# atmegaArduino.net
KiCad netlist of a schematic drawn in EAGLE
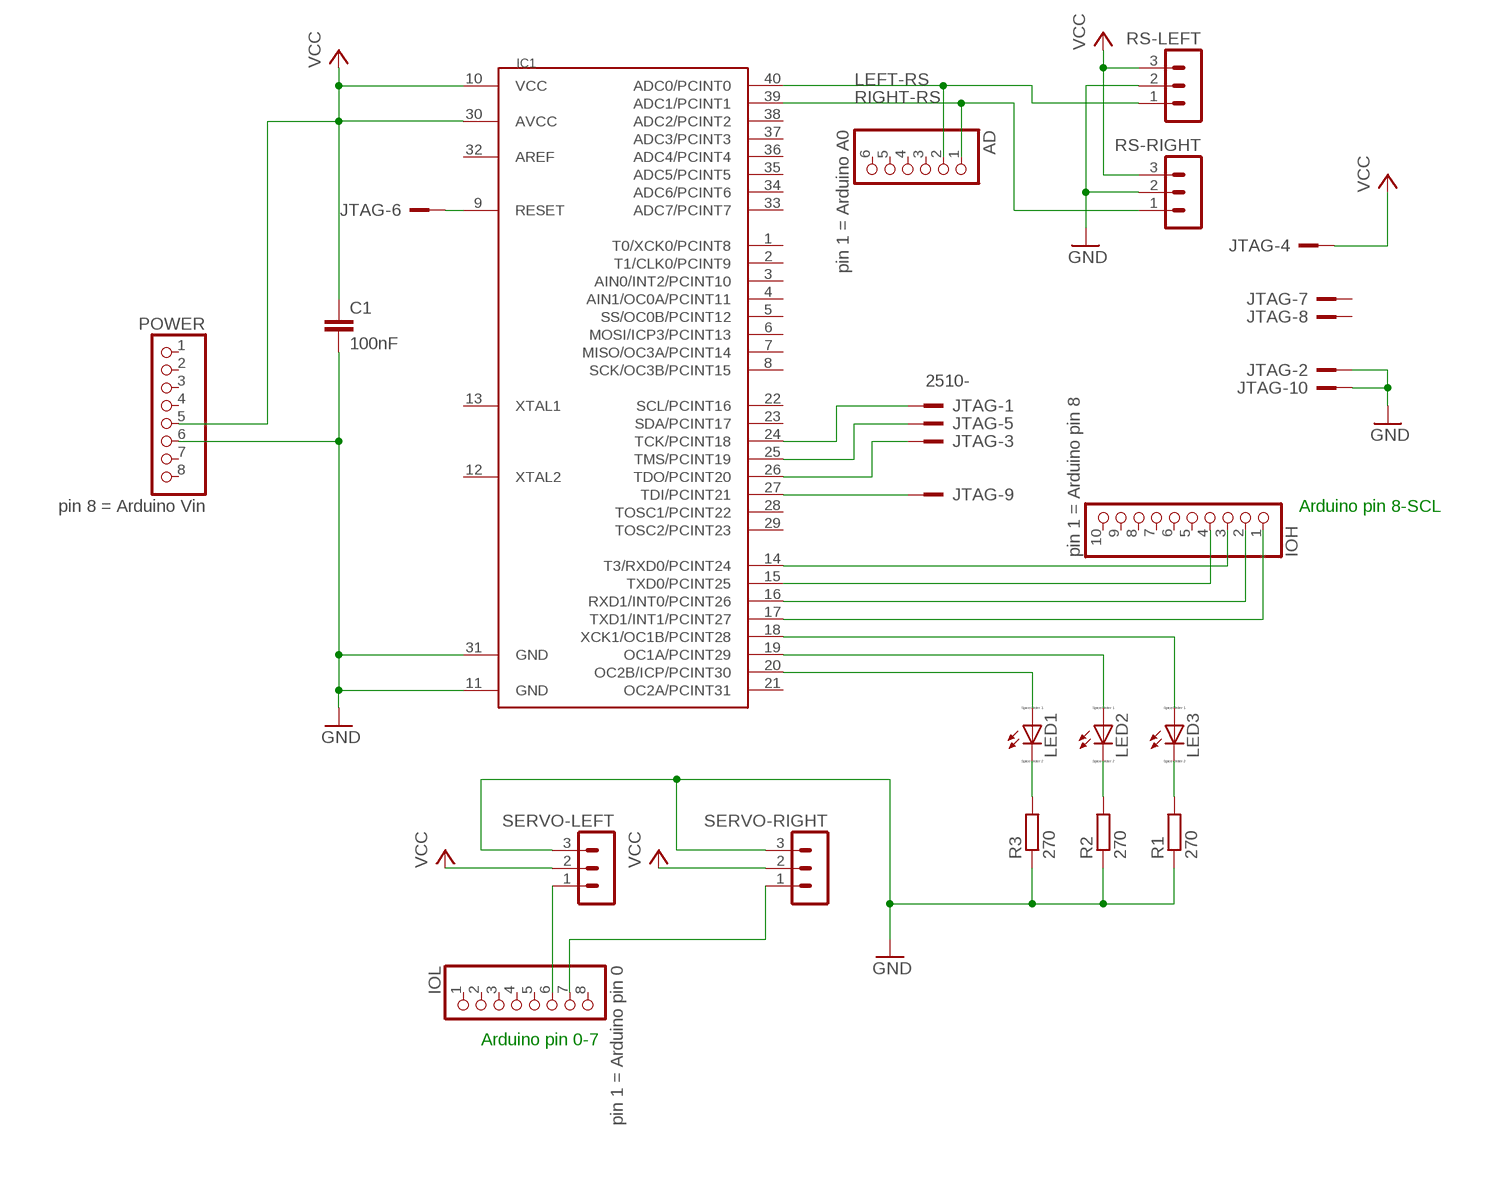
[diagram p0: schematic, sheet 1]

(export (version "E")
  (design (tool "Eeschema 10.0.6"))
  (components
    (comp (ref "AD")
      (value "pin 1 = Arduino A0")
      (footprint "eagle-import:1X06_90")
      (libsource (lib "eagle-import") (part "PINHD-1X6/90"))
    )
    (comp (ref "C1")
      (value "100nF")
      (footprint "eagle-import:C050-025X075")
      (libsource (lib "eagle-import") (part "C-EU050-025X075"))
    )
    (comp (ref "IC1")
      (value "MEGA1284P")
      (footprint "eagle-import:DIL40")
      (libsource (lib "eagle-import") (part "MEGA1284P"))
    )
    (comp (ref "IOH")
      (value "pin 1 = Arduino pin 8")
      (footprint "eagle-import:1X10_90")
      (libsource (lib "eagle-import") (part "PINHD-1X10/90"))
    )
    (comp (ref "IOL")
      (value "pin 1 = Arduino pin 0")
      (footprint "eagle-import:1X08_90")
      (libsource (lib "eagle-import") (part "PINHD-1X8/90"))
    )
    (comp (ref "JTAG")
      (value "2510-")
      (footprint "eagle-import:PAK100_2500-10")
      (fields (field (name "MF") "3M") (field (name "MPN") "2510-6002UB"))
      (libsource (lib "eagle-import") (part "2510-"))
    )
    (comp (ref "LED1")
      (value "LED_ELD260")
      (footprint "eagle-import:LED_LD260")
      (libsource (lib "eagle-import") (part "LED_ELD260"))
    )
    (comp (ref "LED2")
      (value "LED_ELD260")
      (footprint "eagle-import:LED_LD260")
      (libsource (lib "eagle-import") (part "LED_ELD260"))
    )
    (comp (ref "LED3")
      (value "LED_ELD260")
      (footprint "eagle-import:LED_LD260")
      (libsource (lib "eagle-import") (part "LED_ELD260"))
    )
    (comp (ref "POWER")
      (value "pin 8 = Arduino Vin")
      (footprint "eagle-import:1X08_90")
      (libsource (lib "eagle-import") (part "PINHD-1X8/90"))
    )
    (comp (ref "R1")
      (value "270")
      (footprint "eagle-import:0204_5")
      (libsource (lib "eagle-import") (part "R-EU_0204/5"))
    )
    (comp (ref "R2")
      (value "270")
      (footprint "eagle-import:0204_5")
      (libsource (lib "eagle-import") (part "R-EU_0204/5"))
    )
    (comp (ref "R3")
      (value "270")
      (footprint "eagle-import:0204_5")
      (libsource (lib "eagle-import") (part "R-EU_0204/5"))
    )
    (comp (ref "RS-LEFT")
      (value "MA03-1")
      (footprint "eagle-import:MA03-1")
      (libsource (lib "eagle-import") (part "MA03-1"))
    )
    (comp (ref "RS-RIGHT")
      (value "MA03-1")
      (footprint "eagle-import:MA03-1")
      (libsource (lib "eagle-import") (part "MA03-1"))
    )
    (comp (ref "SERVO-LEFT")
      (value "MA03-1")
      (footprint "eagle-import:MA03-1")
      (libsource (lib "eagle-import") (part "MA03-1"))
    )
    (comp (ref "SERVO-RIGHT")
      (value "MA03-1")
      (footprint "eagle-import:MA03-1")
      (libsource (lib "eagle-import") (part "MA03-1"))
    )
  )
  (nets
    (net (code "1") (name "/LEFT-RS") (class "Default")
      (node (ref "AD") (pin "2") (pinfunction "2_2") (pintype "passive"))
      (node (ref "IC1") (pin "40") (pinfunction "ADC0/PCINT0_40") (pintype "bidirectional"))
      (node (ref "RS-LEFT") (pin "1") (pinfunction "1_1") (pintype "passive"))
    )
    (net (code "2") (name "/RIGHT-RS") (class "Default")
      (node (ref "AD") (pin "1") (pinfunction "1_1") (pintype "passive"))
      (node (ref "IC1") (pin "39") (pinfunction "ADC1/PCINT1_39") (pintype "bidirectional"))
      (node (ref "RS-RIGHT") (pin "1") (pinfunction "1_1") (pintype "passive"))
    )
    (net (code "3") (name "GND") (class "Default")
      (node (ref "C1") (pin "2") (pinfunction "2_2") (pintype "passive"))
      (node (ref "IC1") (pin "11") (pinfunction "GND_11") (pintype "bidirectional"))
      (node (ref "IC1") (pin "31") (pinfunction "GND_31") (pintype "bidirectional"))
      (node (ref "JTAG") (pin "10") (pinfunction "KL_10") (pintype "passive"))
      (node (ref "JTAG") (pin "2") (pinfunction "KL_2") (pintype "passive"))
      (node (ref "POWER") (pin "6") (pinfunction "6_6") (pintype "passive"))
      (node (ref "R1") (pin "1") (pinfunction "1_1") (pintype "passive"))
      (node (ref "R2") (pin "1") (pinfunction "1_1") (pintype "passive"))
      (node (ref "R3") (pin "1") (pinfunction "1_1") (pintype "passive"))
      (node (ref "RS-LEFT") (pin "2") (pinfunction "2_2") (pintype "passive"))
      (node (ref "RS-RIGHT") (pin "2") (pinfunction "2_2") (pintype "passive"))
      (node (ref "SERVO-LEFT") (pin "3") (pinfunction "3_3") (pintype "passive"))
      (node (ref "SERVO-RIGHT") (pin "3") (pinfunction "3_3") (pintype "passive"))
    )
    (net (code "4") (name "Net-(IC1-OC1A{slash}PCINT29)") (class "Default")
      (node (ref "IC1") (pin "19") (pinfunction "OC1A/PCINT29_19") (pintype "bidirectional"))
      (node (ref "LED2") (pin "A") (pinfunction "A_A") (pintype "passive"))
    )
    (net (code "5") (name "Net-(IC1-OC2B{slash}ICP{slash}PCINT30)") (class "Default")
      (node (ref "IC1") (pin "20") (pinfunction "OC2B/ICP/PCINT30_20") (pintype "bidirectional"))
      (node (ref "LED1") (pin "A") (pinfunction "A_A") (pintype "passive"))
    )
    (net (code "6") (name "Net-(IC1-RESET)") (class "Default")
      (node (ref "IC1") (pin "9") (pinfunction "RESET_9") (pintype "bidirectional"))
      (node (ref "JTAG") (pin "6") (pinfunction "KL_6") (pintype "passive"))
    )
    (net (code "7") (name "Net-(IC1-RXD1{slash}INT0{slash}PCINT26)") (class "Default")
      (node (ref "IC1") (pin "16") (pinfunction "RXD1/INT0/PCINT26_16") (pintype "bidirectional"))
      (node (ref "IOH") (pin "2") (pinfunction "2_2") (pintype "passive"))
    )
    (net (code "8") (name "Net-(IC1-T3{slash}RXD0{slash}PCINT24)") (class "Default")
      (node (ref "IC1") (pin "14") (pinfunction "T3/RXD0/PCINT24_14") (pintype "bidirectional"))
      (node (ref "IOH") (pin "3") (pinfunction "3_3") (pintype "passive"))
    )
    (net (code "9") (name "Net-(IC1-TCK{slash}PCINT18)") (class "Default")
      (node (ref "IC1") (pin "24") (pinfunction "TCK/PCINT18_24") (pintype "bidirectional"))
      (node (ref "JTAG") (pin "1") (pinfunction "KL_1") (pintype "passive"))
    )
    (net (code "10") (name "Net-(IC1-TDI{slash}PCINT21)") (class "Default")
      (node (ref "IC1") (pin "27") (pinfunction "TDI/PCINT21_27") (pintype "bidirectional"))
      (node (ref "JTAG") (pin "9") (pinfunction "KL_9") (pintype "passive"))
    )
    (net (code "11") (name "Net-(IC1-TDO{slash}PCINT20)") (class "Default")
      (node (ref "IC1") (pin "26") (pinfunction "TDO/PCINT20_26") (pintype "bidirectional"))
      (node (ref "JTAG") (pin "3") (pinfunction "KL_3") (pintype "passive"))
    )
    (net (code "12") (name "Net-(IC1-TMS{slash}PCINT19)") (class "Default")
      (node (ref "IC1") (pin "25") (pinfunction "TMS/PCINT19_25") (pintype "bidirectional"))
      (node (ref "JTAG") (pin "5") (pinfunction "KL_5") (pintype "passive"))
    )
    (net (code "13") (name "Net-(IC1-TXD0{slash}PCINT25)") (class "Default")
      (node (ref "IC1") (pin "15") (pinfunction "TXD0/PCINT25_15") (pintype "bidirectional"))
      (node (ref "IOH") (pin "4") (pinfunction "4_4") (pintype "passive"))
    )
    (net (code "14") (name "Net-(IC1-TXD1{slash}INT1{slash}PCINT27)") (class "Default")
      (node (ref "IC1") (pin "17") (pinfunction "TXD1/INT1/PCINT27_17") (pintype "bidirectional"))
      (node (ref "IOH") (pin "1") (pinfunction "1_1") (pintype "passive"))
    )
    (net (code "15") (name "Net-(IC1-XCK1{slash}OC1B{slash}PCINT28)") (class "Default")
      (node (ref "IC1") (pin "18") (pinfunction "XCK1/OC1B/PCINT28_18") (pintype "bidirectional"))
      (node (ref "LED3") (pin "A") (pinfunction "A_A") (pintype "passive"))
    )
    (net (code "16") (name "Net-(IOL-Pad6)") (class "Default")
      (node (ref "IOL") (pin "6") (pinfunction "6_6") (pintype "passive"))
      (node (ref "SERVO-LEFT") (pin "1") (pinfunction "1_1") (pintype "passive"))
    )
    (net (code "17") (name "Net-(IOL-Pad7)") (class "Default")
      (node (ref "IOL") (pin "7") (pinfunction "7_7") (pintype "passive"))
      (node (ref "SERVO-RIGHT") (pin "1") (pinfunction "1_1") (pintype "passive"))
    )
    (net (code "18") (name "Net-(LED1-C)") (class "Default")
      (node (ref "LED1") (pin "K") (pinfunction "C_K") (pintype "passive"))
      (node (ref "R3") (pin "2") (pinfunction "2_2") (pintype "passive"))
    )
    (net (code "19") (name "Net-(LED2-C)") (class "Default")
      (node (ref "LED2") (pin "K") (pinfunction "C_K") (pintype "passive"))
      (node (ref "R2") (pin "2") (pinfunction "2_2") (pintype "passive"))
    )
    (net (code "20") (name "Net-(LED3-C)") (class "Default")
      (node (ref "LED3") (pin "K") (pinfunction "C_K") (pintype "passive"))
      (node (ref "R1") (pin "2") (pinfunction "2_2") (pintype "passive"))
    )
    (net (code "21") (name "VCC") (class "Default")
      (node (ref "C1") (pin "1") (pinfunction "1_1") (pintype "passive"))
      (node (ref "IC1") (pin "10") (pinfunction "VCC_10") (pintype "bidirectional"))
      (node (ref "IC1") (pin "30") (pinfunction "AVCC_30") (pintype "bidirectional"))
      (node (ref "JTAG") (pin "4") (pinfunction "KL_4") (pintype "passive"))
      (node (ref "POWER") (pin "5") (pinfunction "5_5") (pintype "passive"))
      (node (ref "RS-LEFT") (pin "3") (pinfunction "3_3") (pintype "passive"))
      (node (ref "RS-RIGHT") (pin "3") (pinfunction "3_3") (pintype "passive"))
      (node (ref "SERVO-LEFT") (pin "2") (pinfunction "2_2") (pintype "passive"))
      (node (ref "SERVO-RIGHT") (pin "2") (pinfunction "2_2") (pintype "passive"))
    )
    (net (code "22") (name "unconnected-(AD-Pad3)") (class "Default")
      (node (ref "AD") (pin "3") (pinfunction "3_3") (pintype "passive"))
    )
    (net (code "23") (name "unconnected-(AD-Pad4)") (class "Default")
      (node (ref "AD") (pin "4") (pinfunction "4_4") (pintype "passive"))
    )
    (net (code "24") (name "unconnected-(AD-Pad5)") (class "Default")
      (node (ref "AD") (pin "5") (pinfunction "5_5") (pintype "passive"))
    )
    (net (code "25") (name "unconnected-(AD-Pad6)") (class "Default")
      (node (ref "AD") (pin "6") (pinfunction "6_6") (pintype "passive"))
    )
    (net (code "26") (name "unconnected-(IC1-ADC2{slash}PCINT2-Pad38)") (class "Default")
      (node (ref "IC1") (pin "38") (pinfunction "ADC2/PCINT2_38") (pintype "bidirectional"))
    )
    (net (code "27") (name "unconnected-(IC1-ADC3{slash}PCINT3-Pad37)") (class "Default")
      (node (ref "IC1") (pin "37") (pinfunction "ADC3/PCINT3_37") (pintype "bidirectional"))
    )
    (net (code "28") (name "unconnected-(IC1-ADC4{slash}PCINT4-Pad36)") (class "Default")
      (node (ref "IC1") (pin "36") (pinfunction "ADC4/PCINT4_36") (pintype "bidirectional"))
    )
    (net (code "29") (name "unconnected-(IC1-ADC5{slash}PCINT5-Pad35)") (class "Default")
      (node (ref "IC1") (pin "35") (pinfunction "ADC5/PCINT5_35") (pintype "bidirectional"))
    )
    (net (code "30") (name "unconnected-(IC1-ADC6{slash}PCINT6-Pad34)") (class "Default")
      (node (ref "IC1") (pin "34") (pinfunction "ADC6/PCINT6_34") (pintype "bidirectional"))
    )
    (net (code "31") (name "unconnected-(IC1-ADC7{slash}PCINT7-Pad33)") (class "Default")
      (node (ref "IC1") (pin "33") (pinfunction "ADC7/PCINT7_33") (pintype "bidirectional"))
    )
    (net (code "32") (name "unconnected-(IC1-AIN0{slash}INT2{slash}PCINT10-Pad3)") (class "Default")
      (node (ref "IC1") (pin "3") (pinfunction "AIN0/INT2/PCINT10_3") (pintype "bidirectional"))
    )
    (net (code "33") (name "unconnected-(IC1-AIN1{slash}OC0A{slash}PCINT11-Pad4)") (class "Default")
      (node (ref "IC1") (pin "4") (pinfunction "AIN1/OC0A/PCINT11_4") (pintype "bidirectional"))
    )
    (net (code "34") (name "unconnected-(IC1-AREF-Pad32)") (class "Default")
      (node (ref "IC1") (pin "32") (pinfunction "AREF_32") (pintype "bidirectional"))
    )
    (net (code "35") (name "unconnected-(IC1-MISO{slash}OC3A{slash}PCINT14-Pad7)") (class "Default")
      (node (ref "IC1") (pin "7") (pinfunction "MISO/OC3A/PCINT14_7") (pintype "bidirectional"))
    )
    (net (code "36") (name "unconnected-(IC1-MOSI{slash}ICP3{slash}PCINT13-Pad6)") (class "Default")
      (node (ref "IC1") (pin "6") (pinfunction "MOSI/ICP3/PCINT13_6") (pintype "bidirectional"))
    )
    (net (code "37") (name "unconnected-(IC1-OC2A{slash}PCINT31-Pad21)") (class "Default")
      (node (ref "IC1") (pin "21") (pinfunction "OC2A/PCINT31_21") (pintype "bidirectional"))
    )
    (net (code "38") (name "unconnected-(IC1-SCK{slash}OC3B{slash}PCINT15-Pad8)") (class "Default")
      (node (ref "IC1") (pin "8") (pinfunction "SCK/OC3B/PCINT15_8") (pintype "bidirectional"))
    )
    (net (code "39") (name "unconnected-(IC1-SCL{slash}PCINT16-Pad22)") (class "Default")
      (node (ref "IC1") (pin "22") (pinfunction "SCL/PCINT16_22") (pintype "bidirectional"))
    )
    (net (code "40") (name "unconnected-(IC1-SDA{slash}PCINT17-Pad23)") (class "Default")
      (node (ref "IC1") (pin "23") (pinfunction "SDA/PCINT17_23") (pintype "bidirectional"))
    )
    (net (code "41") (name "unconnected-(IC1-SS{slash}OC0B{slash}PCINT12-Pad5)") (class "Default")
      (node (ref "IC1") (pin "5") (pinfunction "SS/OC0B/PCINT12_5") (pintype "bidirectional"))
    )
    (net (code "42") (name "unconnected-(IC1-T0{slash}XCK0{slash}PCINT8-Pad1)") (class "Default")
      (node (ref "IC1") (pin "1") (pinfunction "T0/XCK0/PCINT8_1") (pintype "bidirectional"))
    )
    (net (code "43") (name "unconnected-(IC1-T1{slash}CLK0{slash}PCINT9-Pad2)") (class "Default")
      (node (ref "IC1") (pin "2") (pinfunction "T1/CLK0/PCINT9_2") (pintype "bidirectional"))
    )
    (net (code "44") (name "unconnected-(IC1-TOSC1{slash}PCINT22-Pad28)") (class "Default")
      (node (ref "IC1") (pin "28") (pinfunction "TOSC1/PCINT22_28") (pintype "bidirectional"))
    )
    (net (code "45") (name "unconnected-(IC1-TOSC2{slash}PCINT23-Pad29)") (class "Default")
      (node (ref "IC1") (pin "29") (pinfunction "TOSC2/PCINT23_29") (pintype "bidirectional"))
    )
    (net (code "46") (name "unconnected-(IC1-XTAL1-Pad13)") (class "Default")
      (node (ref "IC1") (pin "13") (pinfunction "XTAL1_13") (pintype "bidirectional"))
    )
    (net (code "47") (name "unconnected-(IC1-XTAL2-Pad12)") (class "Default")
      (node (ref "IC1") (pin "12") (pinfunction "XTAL2_12") (pintype "bidirectional"))
    )
    (net (code "48") (name "unconnected-(IOH-Pad5)") (class "Default")
      (node (ref "IOH") (pin "5") (pinfunction "5_5") (pintype "passive"))
    )
    (net (code "49") (name "unconnected-(IOH-Pad6)") (class "Default")
      (node (ref "IOH") (pin "6") (pinfunction "6_6") (pintype "passive"))
    )
    (net (code "50") (name "unconnected-(IOH-Pad7)") (class "Default")
      (node (ref "IOH") (pin "7") (pinfunction "7_7") (pintype "passive"))
    )
    (net (code "51") (name "unconnected-(IOH-Pad8)") (class "Default")
      (node (ref "IOH") (pin "8") (pinfunction "8_8") (pintype "passive"))
    )
    (net (code "52") (name "unconnected-(IOH-Pad9)") (class "Default")
      (node (ref "IOH") (pin "9") (pinfunction "9_9") (pintype "passive"))
    )
    (net (code "53") (name "unconnected-(IOH-Pad10)") (class "Default")
      (node (ref "IOH") (pin "10") (pinfunction "10_10") (pintype "passive"))
    )
    (net (code "54") (name "unconnected-(IOL-Pad1)") (class "Default")
      (node (ref "IOL") (pin "1") (pinfunction "1_1") (pintype "passive"))
    )
    (net (code "55") (name "unconnected-(IOL-Pad2)") (class "Default")
      (node (ref "IOL") (pin "2") (pinfunction "2_2") (pintype "passive"))
    )
    (net (code "56") (name "unconnected-(IOL-Pad3)") (class "Default")
      (node (ref "IOL") (pin "3") (pinfunction "3_3") (pintype "passive"))
    )
    (net (code "57") (name "unconnected-(IOL-Pad4)") (class "Default")
      (node (ref "IOL") (pin "4") (pinfunction "4_4") (pintype "passive"))
    )
    (net (code "58") (name "unconnected-(IOL-Pad5)") (class "Default")
      (node (ref "IOL") (pin "5") (pinfunction "5_5") (pintype "passive"))
    )
    (net (code "59") (name "unconnected-(IOL-Pad8)") (class "Default")
      (node (ref "IOL") (pin "8") (pinfunction "8_8") (pintype "passive"))
    )
    (net (code "60") (name "unconnected-(JTAGH-KL-Pad7)") (class "Default")
      (node (ref "JTAG") (pin "7") (pinfunction "KL_7") (pintype "passive"))
    )
    (net (code "61") (name "unconnected-(JTAGI-KL-Pad8)") (class "Default")
      (node (ref "JTAG") (pin "8") (pinfunction "KL_8") (pintype "passive"))
    )
    (net (code "62") (name "unconnected-(POWER-Pad1)") (class "Default")
      (node (ref "POWER") (pin "1") (pinfunction "1_1") (pintype "passive"))
    )
    (net (code "63") (name "unconnected-(POWER-Pad2)") (class "Default")
      (node (ref "POWER") (pin "2") (pinfunction "2_2") (pintype "passive"))
    )
    (net (code "64") (name "unconnected-(POWER-Pad3)") (class "Default")
      (node (ref "POWER") (pin "3") (pinfunction "3_3") (pintype "passive"))
    )
    (net (code "65") (name "unconnected-(POWER-Pad4)") (class "Default")
      (node (ref "POWER") (pin "4") (pinfunction "4_4") (pintype "passive"))
    )
    (net (code "66") (name "unconnected-(POWER-Pad7)") (class "Default")
      (node (ref "POWER") (pin "7") (pinfunction "7_7") (pintype "passive"))
    )
    (net (code "67") (name "unconnected-(POWER-Pad8)") (class "Default")
      (node (ref "POWER") (pin "8") (pinfunction "8_8") (pintype "passive"))
    )
  )
)
